# estop.net
KiCad netlist of a schematic drawn in EasyEDA Pro
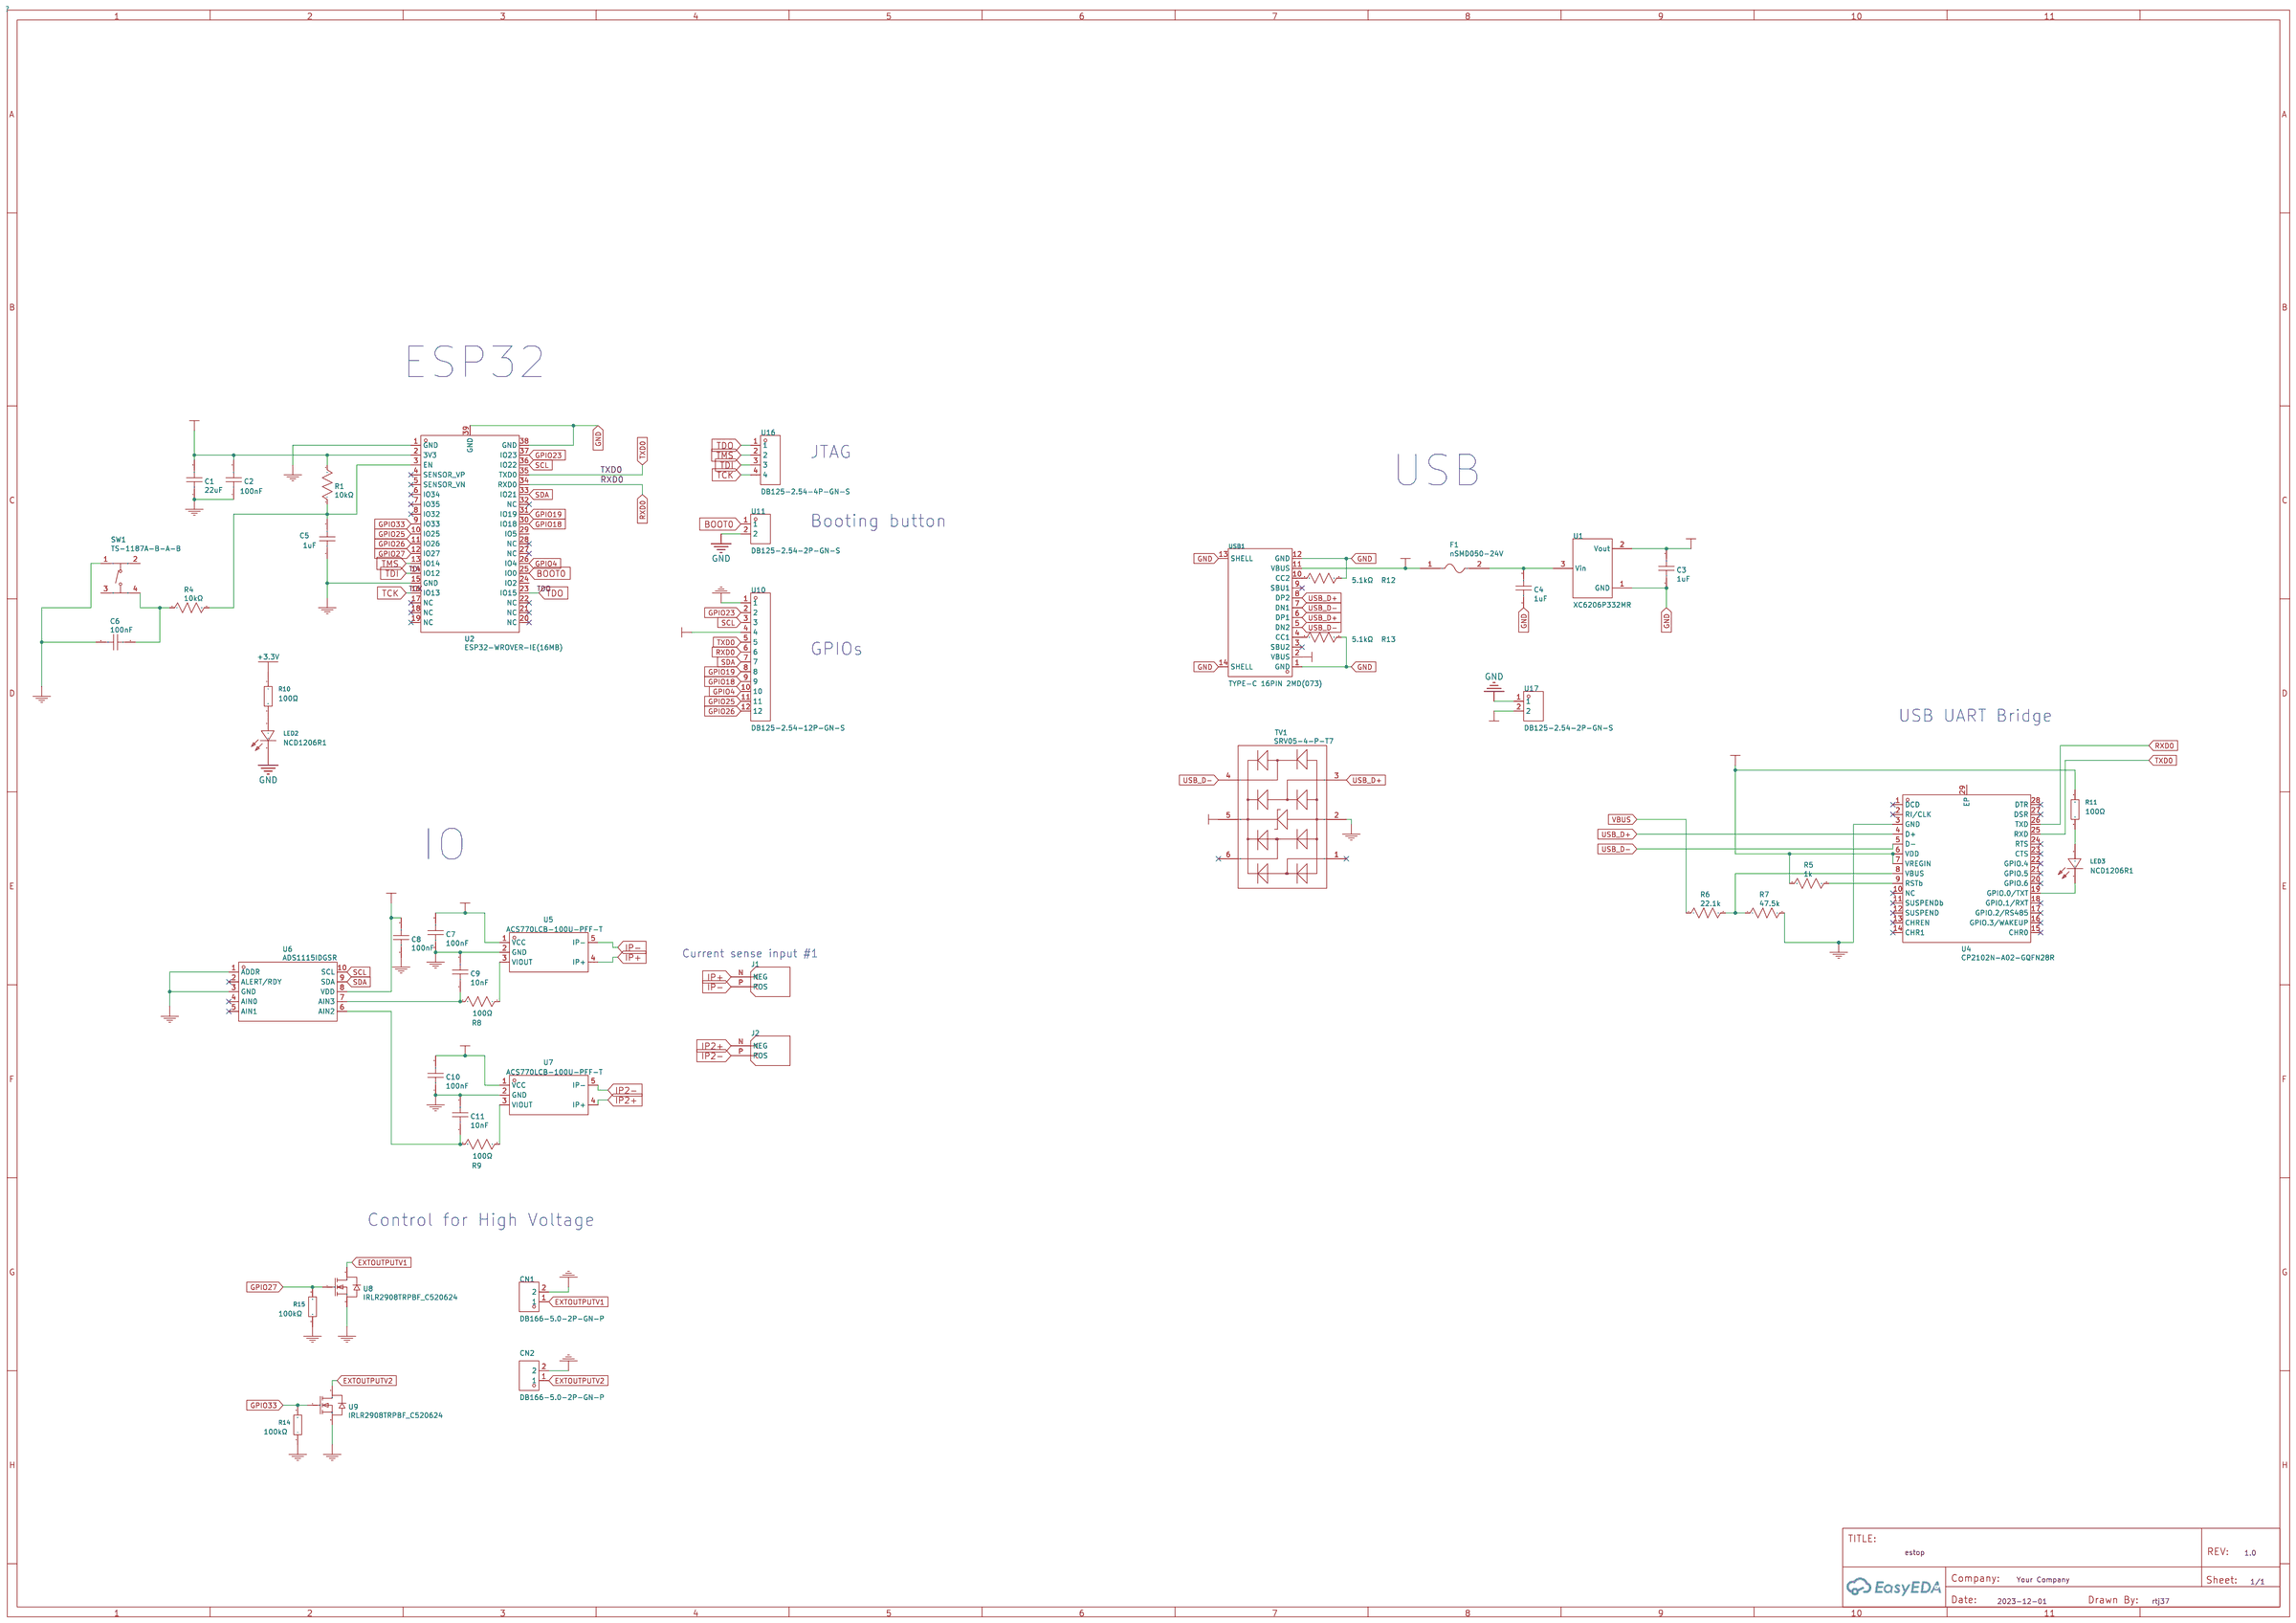
[diagram p0: schematic sheet]

(export (version "E")
  (design (tool "Eeschema 10.0.6"))
  (components
    (comp (ref "C1")
      (value "22uF")
      (footprint "easyedapro:C1206")
      (fields
        (field (name "Manufacturer Part") "CL31A226KAHNNNE")
        (field (name "Manufacturer") "SAMSUNG(三星)")
      )
      (libsource (lib "easyedapro") (part "22u"))
    )
    (comp (ref "C2")
      (value "100nF")
      (footprint "easyedapro:C1206")
      (fields (field (name "Manufacturer Part") "1206B104K500NT") (field (name "Manufacturer") "FH(风华)"))
      (libsource (lib "easyedapro") (part "0.1u"))
    )
    (comp (ref "C3")
      (value "1uF")
      (footprint "easyedapro:C0603")
      (fields (field (name "Manufacturer Part") "1206B105K500NT") (field (name "Manufacturer") "FH(风华)"))
      (libsource (lib "easyedapro") (part "1u"))
    )
    (comp (ref "C4")
      (value "1uF")
      (footprint "easyedapro:C0603")
      (fields (field (name "Manufacturer Part") "1206B105K500NT") (field (name "Manufacturer") "FH(风华)"))
      (libsource (lib "easyedapro") (part "1u"))
    )
    (comp (ref "C5")
      (value "1uF")
      (footprint "easyedapro:C0603")
      (fields (field (name "Manufacturer Part") "1206B105K500NT") (field (name "Manufacturer") "FH(风华)"))
      (libsource (lib "easyedapro") (part "1u"))
    )
    (comp (ref "C6")
      (value "100nF")
      (footprint "easyedapro:C1206")
      (fields (field (name "Manufacturer Part") "1206B104K500NT") (field (name "Manufacturer") "FH(风华)"))
      (libsource (lib "easyedapro") (part "0.1u"))
    )
    (comp (ref "C7")
      (value "100nF")
      (footprint "easyedapro:C1206")
      (fields (field (name "Manufacturer Part") "1206B104K500NT") (field (name "Manufacturer") "FH(风华)"))
      (libsource (lib "easyedapro") (part "0.1u"))
    )
    (comp (ref "C8")
      (value "100nF")
      (footprint "easyedapro:C1206")
      (fields (field (name "Manufacturer Part") "1206B104K500NT") (field (name "Manufacturer") "FH(风华)"))
      (libsource (lib "easyedapro") (part "100n"))
    )
    (comp (ref "C9")
      (value "10nF")
      (footprint "easyedapro:C0805")
      (fields (field (name "Manufacturer Part") "1206B103K102CT") (field (name "Manufacturer") "Walsin(华新科)"))
      (libsource (lib "easyedapro") (part "10n"))
    )
    (comp (ref "C10")
      (value "100nF")
      (footprint "easyedapro:C1206")
      (fields (field (name "Manufacturer Part") "1206B104K500NT") (field (name "Manufacturer") "FH(风华)"))
      (libsource (lib "easyedapro") (part "0.1u"))
    )
    (comp (ref "C11")
      (value "10nF")
      (footprint "easyedapro:C0805")
      (fields (field (name "Manufacturer Part") "1206B103K102CT") (field (name "Manufacturer") "Walsin(华新科)"))
      (libsource (lib "easyedapro") (part "10n"))
    )
    (comp (ref "CN1")
      (value "DB166-5.0-2P-GN-P")
      (footprint "easyedapro:CONN-TH_2P-P5.00_DB166-5.0-2P-GN-P")
      (description "Pitch:5mm Number of Pins:2P")
      (fields (field (name "Manufacturer") "DORABO(地博电气)"))
      (libsource (lib "easyedapro") (part "DB166-5.0-2P-GN-P"))
    )
    (comp (ref "CN2")
      (value "DB166-5.0-2P-GN-P")
      (footprint "easyedapro:CONN-TH_2P-P5.00_DB166-5.0-2P-GN-P")
      (description "Pitch:5mm Number of Pins:2P")
      (fields (field (name "Manufacturer") "DORABO(地博电气)"))
      (libsource (lib "easyedapro") (part "DB166-5.0-2P-GN-P"))
    )
    (comp (ref "F1")
      (value "nSMD050-24V")
      (footprint "easyedapro:F1206")
      (fields (field (name "Manufacturer") "台湾陆海"))
      (libsource (lib "easyedapro") (part "nSMD050-24V"))
    )
    (comp (ref "J1")
      (value "XT90PW-F")
      (footprint "easyedapro:AMASS_XT90PW-F")
      (description "\\nSocket, DC supply, XT90, female, PIN:2, on PCBs, THT\\n")
      (libsource (lib "easyedapro") (part "XT90PW-F"))
    )
    (comp (ref "J2")
      (value "XT90PW-F")
      (footprint "easyedapro:AMASS_XT90PW-F")
      (description "\\nSocket, DC supply, XT90, female, PIN:2, on PCBs, THT\\n")
      (libsource (lib "easyedapro") (part "XT90PW-F"))
    )
    (comp (ref "LED2")
      (value "NCD1206R1")
      (footprint "easyedapro:LED1206-R-RD_RED")
      (fields (field (name "Manufacturer") "国星光电"))
      (libsource (lib "easyedapro") (part "FC-3215HRK-620D"))
    )
    (comp (ref "LED3")
      (value "NCD1206R1")
      (footprint "easyedapro:LED1206-R-RD_RED")
      (fields (field (name "Manufacturer") "国星光电"))
      (libsource (lib "easyedapro") (part "FC-3215HRK-620D"))
    )
    (comp (ref "R1")
      (value "10kΩ")
      (footprint "easyedapro:R1206")
      (fields
        (field (name "Manufacturer Part") "1206W4F1002T5E")
        (field (name "Manufacturer") "UNI-ROYAL(厚声)")
      )
      (libsource (lib "easyedapro") (part "10k"))
    )
    (comp (ref "R4")
      (value "10kΩ")
      (footprint "easyedapro:R1206")
      (fields
        (field (name "Manufacturer Part") "1206W4F1002T5E")
        (field (name "Manufacturer") "UNI-ROYAL(厚声)")
      )
      (libsource (lib "easyedapro") (part "0"))
    )
    (comp (ref "R5") (value "1k") (footprint "easyedapro:R1206") (libsource (lib "easyedapro") (part "1k")))
    (comp (ref "R6")
      (value "22.1k")
      (footprint "easyedapro:R1206")
      (libsource (lib "easyedapro") (part "22.1k"))
    )
    (comp (ref "R7")
      (value "47.5k")
      (footprint "easyedapro:R1206")
      (libsource (lib "easyedapro") (part "47.5k"))
    )
    (comp (ref "R8")
      (value "100Ω")
      (footprint "easyedapro:R0603")
      (fields
        (field (name "Manufacturer Part") "1206W4F1000T5E")
        (field (name "Manufacturer") "UNI-ROYAL(厚声)")
      )
      (libsource (lib "easyedapro") (part "100"))
    )
    (comp (ref "R9")
      (value "100Ω")
      (footprint "easyedapro:R0603")
      (fields
        (field (name "Manufacturer Part") "1206W4F1000T5E")
        (field (name "Manufacturer") "UNI-ROYAL(厚声)")
      )
      (libsource (lib "easyedapro") (part "100"))
    )
    (comp (ref "R10")
      (value "100Ω")
      (footprint "easyedapro:R1206")
      (fields
        (field (name "Manufacturer Part") "1206W4F1000T5E")
        (field (name "Manufacturer") "UNI-ROYAL(厚声)")
      )
      (libsource (lib "easyedapro") (part "1206W4F1000T5E"))
    )
    (comp (ref "R11")
      (value "100Ω")
      (footprint "easyedapro:R1206")
      (fields
        (field (name "Manufacturer Part") "1206W4F1000T5E")
        (field (name "Manufacturer") "UNI-ROYAL(厚声)")
      )
      (libsource (lib "easyedapro") (part "1206W4F1000T5E"))
    )
    (comp (ref "R12")
      (value "5.1kΩ")
      (footprint "easyedapro:R0603")
      (fields
        (field (name "Manufacturer Part") "1206W4F5101T5E")
        (field (name "Manufacturer") "UNI-ROYAL(厚声)")
      )
      (libsource (lib "easyedapro") (part "5.1k"))
    )
    (comp (ref "R13")
      (value "5.1kΩ")
      (footprint "easyedapro:R0603")
      (fields
        (field (name "Manufacturer Part") "1206W4F5101T5E")
        (field (name "Manufacturer") "UNI-ROYAL(厚声)")
      )
      (libsource (lib "easyedapro") (part "5.1k"))
    )
    (comp (ref "R14")
      (value "100kΩ")
      (footprint "easyedapro:R1206")
      (fields
        (field (name "Manufacturer Part") "1206W4F1003T5E")
        (field (name "Manufacturer") "UNI-ROYAL(厚声)")
      )
      (libsource (lib "easyedapro") (part "1206W4F1003T5E"))
    )
    (comp (ref "R15")
      (value "100kΩ")
      (footprint "easyedapro:R1206")
      (fields
        (field (name "Manufacturer Part") "1206W4F1003T5E")
        (field (name "Manufacturer") "UNI-ROYAL(厚声)")
      )
      (libsource (lib "easyedapro") (part "1206W4F1003T5E"))
    )
    (comp (ref "SW1")
      (value "TS-1187A-B-A-B")
      (footprint "easyedapro:SW-SMD_4P-L5.1-W5.1-P3.70-LS6.5-TL-2")
      (fields (field (name "Manufacturer") "XKB Connectivity(中国星坤)"))
      (libsource (lib "easyedapro") (part "TS-1187A-B-A-B"))
    )
    (comp (ref "TV1")
      (value "SRV05-4-P-T7")
      (footprint "easyedapro:SOT-23-6_L2.9-W1.6-P0.95-LS2.8-BR")
      (fields (field (name "Manufacturer") "PROTEK"))
      (libsource (lib "easyedapro") (part "SRV05-4-P-T7"))
    )
    (comp (ref "U1")
      (value "XC6206P332MR")
      (footprint "easyedapro:SOT-23-3_L2.9-W1.6-P1.90-LS2.8-BR")
      (fields (field (name "Manufacturer") "TOREX(特瑞仕)"))
      (libsource (lib "easyedapro") (part "XC6206P332MR"))
    )
    (comp (ref "U2")
      (value "ESP32-WROVER-IE(16MB)")
      (footprint "easyedapro:WIFI-SMD_ESP32-WROVER-E")
      (fields
        (field (name "Manufacturer Part") "ESP32-WROVER-IE-N16R8")
        (field (name "Manufacturer") "ESPRESSIF(乐鑫)")
      )
      (libsource (lib "easyedapro") (part "ESP32-WROVER-IE(16MB)"))
    )
    (comp (ref "U4")
      (value "CP2102N-A02-GQFN28R")
      (footprint "easyedapro:QFN-28_L5.0-W5.0-P0.50-TL-EP3.3")
      (fields (field (name "Manufacturer") "SILICON LABS(芯科)"))
      (libsource (lib "easyedapro") (part "CP2102N-A02-GQFN28R"))
    )
    (comp (ref "U5")
      (value "ACS770LCB-100U-PFF-T")
      (footprint "easyedapro:SENSOR-TH_ACS770LCB-100U-PFF-T")
      (fields (field (name "Manufacturer") "ALLEGRO(美国埃戈罗)"))
      (libsource (lib "easyedapro") (part "ACS770LCB-100U-PFF-T"))
    )
    (comp (ref "U6")
      (value "ADS1115IDGSR")
      (footprint "easyedapro:MSOP-10_L3.0-W3.0-P0.50-LS5.0-BL")
      (fields (field (name "Manufacturer") "TI(德州仪器)"))
      (libsource (lib "easyedapro") (part "ADS1115IDGSR"))
    )
    (comp (ref "U7")
      (value "ACS770LCB-100U-PFF-T")
      (footprint "easyedapro:SENSOR-TH_ACS770LCB-100U-PFF-T")
      (fields (field (name "Manufacturer") "ALLEGRO(美国埃戈罗)"))
      (libsource (lib "easyedapro") (part "ACS770LCB-100U-PFF-T"))
    )
    (comp (ref "U8")
      (value "IRLR2908TRPBF_C520624")
      (footprint "easyedapro:TO-252-3_L6.5-W6.1-P4.58-LS9.9-BR")
      (fields
        (field (name "Manufacturer Part") "IRLR2908TRPBF")
        (field (name "Manufacturer") "Infineon(英飞凌)")
      )
      (libsource (lib "easyedapro") (part "IRLR2908TRPBF_C520624"))
    )
    (comp (ref "U9")
      (value "IRLR2908TRPBF_C520624")
      (footprint "easyedapro:TO-252-3_L6.5-W6.1-P4.58-LS9.9-BR")
      (fields
        (field (name "Manufacturer Part") "IRLR2908TRPBF")
        (field (name "Manufacturer") "Infineon(英飞凌)")
      )
      (libsource (lib "easyedapro") (part "IRLR2908TRPBF_C520624"))
    )
    (comp (ref "U10")
      (value "DB125-2.54-12P-GN-S")
      (footprint "easyedapro:CONN-TH_DB125-2.54-12P-GN")
      (fields (field (name "Manufacturer") "DORABO(地博电气)"))
      (libsource (lib "easyedapro") (part "DB125-2.54-12P-GN"))
    )
    (comp (ref "U11")
      (value "DB125-2.54-2P-GN-S")
      (footprint "easyedapro:CONN-TH_DB125-2.54-2P-GN")
      (fields (field (name "Manufacturer") "DORABO(地博电气)"))
      (libsource (lib "easyedapro") (part "DB125-2.54-2P-GN"))
    )
    (comp (ref "U16")
      (value "DB125-2.54-4P-GN-S")
      (footprint "easyedapro:CONN-TH_DB125-2.54-4P-GN")
      (fields (field (name "Manufacturer") "DORABO(地博电气)"))
      (libsource (lib "easyedapro") (part "DB125-2.54-4P-GN"))
    )
    (comp (ref "U17")
      (value "DB125-2.54-2P-GN-S")
      (footprint "easyedapro:CONN-TH_DB125-2.54-2P-GN")
      (fields (field (name "Manufacturer") "DORABO(地博电气)"))
      (libsource (lib "easyedapro") (part "DB125-2.54-2P-GN"))
    )
    (comp (ref "USB1")
      (value "TYPE-C 16PIN 2MD(073)")
      (footprint "easyedapro:USB-C-SMD_TYPE-C-6PIN-2MD-073")
      (fields (field (name "Manufacturer") "SHOU HAN(首韩)"))
      (libsource (lib "easyedapro") (part "TYPE-C 16PIN 2MD(073)"))
    )
  )
  (nets
    (net (code "1") (name "+3.3V") (class "Default")
      (node (ref "C1") (pin "2") (pinfunction "2_2") (pintype "unspecified"))
      (node (ref "C2") (pin "2") (pinfunction "2_2") (pintype "unspecified"))
      (node (ref "C3") (pin "2") (pinfunction "2_2") (pintype "unspecified"))
      (node (ref "C8") (pin "2") (pinfunction "2_2") (pintype "unspecified"))
      (node (ref "R1") (pin "2") (pinfunction "2_2") (pintype "unspecified"))
      (node (ref "R10") (pin "1") (pinfunction "1_1") (pintype "input"))
      (node (ref "R11") (pin "1") (pinfunction "1_1") (pintype "input"))
      (node (ref "R5") (pin "1") (pinfunction "1_1") (pintype "unspecified"))
      (node (ref "U1") (pin "2") (pinfunction "Vout_2") (pintype "unspecified"))
      (node (ref "U10") (pin "4") (pinfunction "4_4") (pintype "unspecified"))
      (node (ref "U2") (pin "2") (pinfunction "3V3_2") (pintype "unspecified"))
      (node (ref "U4") (pin "6") (pinfunction "VDD_6") (pintype "unspecified"))
      (node (ref "U4") (pin "7") (pinfunction "VREGIN_7") (pintype "unspecified"))
      (node (ref "U6") (pin "8") (pinfunction "VDD_8") (pintype "unspecified"))
    )
    (net (code "2") (name "BOOT0") (class "Default")
      (node (ref "U11") (pin "1") (pinfunction "1_1") (pintype "unspecified"))
      (node (ref "U2") (pin "25") (pinfunction "IO0_25") (pintype "unspecified"))
    )
    (net (code "3") (name "EXTOUTPUTV1") (class "Default")
      (node (ref "CN1") (pin "1") (pinfunction "1_1") (pintype "unspecified"))
      (node (ref "U8") (pin "2") (pinfunction "D_2") (pintype "unspecified"))
    )
    (net (code "4") (name "EXTOUTPUTV2") (class "Default")
      (node (ref "CN2") (pin "1") (pinfunction "1_1") (pintype "unspecified"))
      (node (ref "U9") (pin "2") (pinfunction "D_2") (pintype "unspecified"))
    )
    (net (code "5") (name "GND") (class "Default")
      (node (ref "C1") (pin "1") (pinfunction "1_1") (pintype "unspecified"))
      (node (ref "C10") (pin "1") (pinfunction "1_1") (pintype "unspecified"))
      (node (ref "C11") (pin "2") (pinfunction "2_2") (pintype "unspecified"))
      (node (ref "C2") (pin "1") (pinfunction "1_1") (pintype "unspecified"))
      (node (ref "C3") (pin "1") (pinfunction "1_1") (pintype "unspecified"))
      (node (ref "C4") (pin "1") (pinfunction "1_1") (pintype "unspecified"))
      (node (ref "C5") (pin "1") (pinfunction "1_1") (pintype "unspecified"))
      (node (ref "C6") (pin "1") (pinfunction "1_1") (pintype "unspecified"))
      (node (ref "C7") (pin "1") (pinfunction "1_1") (pintype "unspecified"))
      (node (ref "C8") (pin "1") (pinfunction "1_1") (pintype "unspecified"))
      (node (ref "C9") (pin "2") (pinfunction "2_2") (pintype "unspecified"))
      (node (ref "CN1") (pin "2") (pinfunction "2_2") (pintype "unspecified"))
      (node (ref "CN2") (pin "2") (pinfunction "2_2") (pintype "unspecified"))
      (node (ref "LED2") (pin "2") (pinfunction "K_2") (pintype "input"))
      (node (ref "R12") (pin "2") (pinfunction "2_2") (pintype "unspecified"))
      (node (ref "R13") (pin "2") (pinfunction "2_2") (pintype "unspecified"))
      (node (ref "R14") (pin "1") (pinfunction "1_1") (pintype "input"))
      (node (ref "R15") (pin "1") (pinfunction "1_1") (pintype "input"))
      (node (ref "R7") (pin "2") (pinfunction "2_2") (pintype "unspecified"))
      (node (ref "SW1") (pin "1") (pinfunction "A_1") (pintype "unspecified"))
      (node (ref "TV1") (pin "2") (pinfunction "2_2") (pintype "input"))
      (node (ref "U1") (pin "1") (pinfunction "GND_1") (pintype "unspecified"))
      (node (ref "U10") (pin "1") (pinfunction "1_1") (pintype "unspecified"))
      (node (ref "U11") (pin "2") (pinfunction "2_2") (pintype "unspecified"))
      (node (ref "U17") (pin "1") (pinfunction "1_1") (pintype "unspecified"))
      (node (ref "U2") (pin "1") (pinfunction "GND_1") (pintype "unspecified"))
      (node (ref "U2") (pin "15") (pinfunction "GND_15") (pintype "unspecified"))
      (node (ref "U2") (pin "38") (pinfunction "GND_38") (pintype "unspecified"))
      (node (ref "U2") (pin "39") (pinfunction "GND_39") (pintype "unspecified"))
      (node (ref "U4") (pin "3") (pinfunction "GND_3") (pintype "unspecified"))
      (node (ref "U5") (pin "2") (pinfunction "GND_2") (pintype "unspecified"))
      (node (ref "U6") (pin "1") (pinfunction "ADDR_1") (pintype "unspecified"))
      (node (ref "U6") (pin "3") (pinfunction "GND_3") (pintype "unspecified"))
      (node (ref "U7") (pin "2") (pinfunction "GND_2") (pintype "unspecified"))
      (node (ref "U8") (pin "3") (pinfunction "S_3") (pintype "unspecified"))
      (node (ref "U9") (pin "3") (pinfunction "S_3") (pintype "unspecified"))
      (node (ref "USB1") (pin "1") (pinfunction "GND_1") (pintype "input"))
      (node (ref "USB1") (pin "12") (pinfunction "GND_12") (pintype "input"))
      (node (ref "USB1") (pin "13") (pinfunction "SHELL_13") (pintype "input"))
      (node (ref "USB1") (pin "14") (pinfunction "SHELL_14") (pintype "input"))
    )
    (net (code "6") (name "GPIO4") (class "Default")
      (node (ref "U10") (pin "10") (pinfunction "10_10") (pintype "unspecified"))
      (node (ref "U2") (pin "26") (pinfunction "IO4_26") (pintype "unspecified"))
    )
    (net (code "7") (name "GPIO18") (class "Default")
      (node (ref "U10") (pin "9") (pinfunction "9_9") (pintype "unspecified"))
      (node (ref "U2") (pin "30") (pinfunction "IO18_30") (pintype "unspecified"))
    )
    (net (code "8") (name "GPIO19") (class "Default")
      (node (ref "U10") (pin "8") (pinfunction "8_8") (pintype "unspecified"))
      (node (ref "U2") (pin "31") (pinfunction "IO19_31") (pintype "unspecified"))
    )
    (net (code "9") (name "GPIO23") (class "Default")
      (node (ref "U10") (pin "2") (pinfunction "2_2") (pintype "unspecified"))
      (node (ref "U2") (pin "37") (pinfunction "IO23_37") (pintype "unspecified"))
    )
    (net (code "10") (name "GPIO25") (class "Default")
      (node (ref "U10") (pin "11") (pinfunction "11_11") (pintype "unspecified"))
      (node (ref "U2") (pin "10") (pinfunction "IO25_10") (pintype "unspecified"))
    )
    (net (code "11") (name "GPIO26") (class "Default")
      (node (ref "U10") (pin "12") (pinfunction "12_12") (pintype "unspecified"))
      (node (ref "U2") (pin "11") (pinfunction "IO26_11") (pintype "unspecified"))
    )
    (net (code "12") (name "GPIO27") (class "Default")
      (node (ref "R15") (pin "2") (pinfunction "2_2") (pintype "input"))
      (node (ref "U2") (pin "12") (pinfunction "IO27_12") (pintype "unspecified"))
      (node (ref "U8") (pin "1") (pinfunction "G_1") (pintype "unspecified"))
    )
    (net (code "13") (name "GPIO33") (class "Default")
      (node (ref "R14") (pin "2") (pinfunction "2_2") (pintype "input"))
      (node (ref "U2") (pin "9") (pinfunction "IO33_9") (pintype "unspecified"))
      (node (ref "U9") (pin "1") (pinfunction "G_1") (pintype "unspecified"))
    )
    (net (code "14") (name "IP+") (class "Default")
      (node (ref "J1") (pin "N") (pinfunction "NEG_N") (pintype "unspecified"))
      (node (ref "U5") (pin "4") (pinfunction "IP+_4") (pintype "unspecified"))
    )
    (net (code "15") (name "IP-") (class "Default")
      (node (ref "J1") (pin "P") (pinfunction "POS_P") (pintype "unspecified"))
      (node (ref "U5") (pin "5") (pinfunction "IP-_5") (pintype "unspecified"))
    )
    (net (code "16") (name "IP2+") (class "Default")
      (node (ref "J2") (pin "N") (pinfunction "NEG_N") (pintype "unspecified"))
      (node (ref "U7") (pin "4") (pinfunction "IP+_4") (pintype "unspecified"))
    )
    (net (code "17") (name "IP2-") (class "Default")
      (node (ref "J2") (pin "P") (pinfunction "POS_P") (pintype "unspecified"))
      (node (ref "U7") (pin "5") (pinfunction "IP-_5") (pintype "unspecified"))
    )
    (net (code "18") (name "Net-(LED2-A)") (class "Default")
      (node (ref "LED2") (pin "1") (pinfunction "A_1") (pintype "input"))
      (node (ref "R10") (pin "2") (pinfunction "2_2") (pintype "input"))
    )
    (net (code "19") (name "Net-(LED3-A)") (class "Default")
      (node (ref "LED3") (pin "1") (pinfunction "A_1") (pintype "input"))
      (node (ref "R11") (pin "2") (pinfunction "2_2") (pintype "input"))
    )
    (net (code "20") (name "Net-(LED3-K)") (class "Default")
      (node (ref "LED3") (pin "2") (pinfunction "K_2") (pintype "input"))
      (node (ref "U4") (pin "19") (pinfunction "GPIO.0/TXT_19") (pintype "unspecified"))
    )
    (net (code "21") (name "Net-(SW1-D)") (class "Default")
      (node (ref "C6") (pin "2") (pinfunction "2_2") (pintype "unspecified"))
      (node (ref "R4") (pin "1") (pinfunction "1_1") (pintype "unspecified"))
      (node (ref "SW1") (pin "4") (pinfunction "D_4") (pintype "unspecified"))
    )
    (net (code "22") (name "Net-(U1-Vin)") (class "Default")
      (node (ref "C4") (pin "2") (pinfunction "2_2") (pintype "unspecified"))
      (node (ref "F1") (pin "2") (pinfunction "2_2") (pintype "unspecified"))
      (node (ref "U1") (pin "3") (pinfunction "Vin_3") (pintype "unspecified"))
    )
    (net (code "23") (name "Net-(U2-EN)") (class "Default")
      (node (ref "C5") (pin "2") (pinfunction "2_2") (pintype "unspecified"))
      (node (ref "R1") (pin "1") (pinfunction "1_1") (pintype "unspecified"))
      (node (ref "R4") (pin "2") (pinfunction "2_2") (pintype "unspecified"))
      (node (ref "U2") (pin "3") (pinfunction "EN_3") (pintype "unspecified"))
    )
    (net (code "24") (name "Net-(U4-RSTb)") (class "Default")
      (node (ref "R5") (pin "2") (pinfunction "2_2") (pintype "unspecified"))
      (node (ref "U4") (pin "9") (pinfunction "RSTb_9") (pintype "unspecified"))
    )
    (net (code "25") (name "Net-(U4-VBUS)") (class "Default")
      (node (ref "R6") (pin "2") (pinfunction "2_2") (pintype "unspecified"))
      (node (ref "R7") (pin "1") (pinfunction "1_1") (pintype "unspecified"))
      (node (ref "U4") (pin "8") (pinfunction "VBUS_8") (pintype "unspecified"))
    )
    (net (code "26") (name "Net-(U5-VIOUT)") (class "Default")
      (node (ref "R8") (pin "1") (pinfunction "1_1") (pintype "unspecified"))
      (node (ref "U5") (pin "3") (pinfunction "VIOUT_3") (pintype "unspecified"))
    )
    (net (code "27") (name "Net-(U6-AIN2)") (class "Default")
      (node (ref "C11") (pin "1") (pinfunction "1_1") (pintype "unspecified"))
      (node (ref "R9") (pin "2") (pinfunction "2_2") (pintype "unspecified"))
      (node (ref "U6") (pin "6") (pinfunction "AIN2_6") (pintype "unspecified"))
    )
    (net (code "28") (name "Net-(U6-AIN3)") (class "Default")
      (node (ref "C9") (pin "1") (pinfunction "1_1") (pintype "unspecified"))
      (node (ref "R8") (pin "2") (pinfunction "2_2") (pintype "unspecified"))
      (node (ref "U6") (pin "7") (pinfunction "AIN3_7") (pintype "unspecified"))
    )
    (net (code "29") (name "Net-(U7-VIOUT)") (class "Default")
      (node (ref "R9") (pin "1") (pinfunction "1_1") (pintype "unspecified"))
      (node (ref "U7") (pin "3") (pinfunction "VIOUT_3") (pintype "unspecified"))
    )
    (net (code "30") (name "Net-(USB1-CC1)") (class "Default")
      (node (ref "R13") (pin "1") (pinfunction "1_1") (pintype "unspecified"))
      (node (ref "USB1") (pin "4") (pinfunction "CC1_4") (pintype "input"))
    )
    (net (code "31") (name "Net-(USB1-CC2)") (class "Default")
      (node (ref "R12") (pin "1") (pinfunction "1_1") (pintype "unspecified"))
      (node (ref "USB1") (pin "10") (pinfunction "CC2_10") (pintype "input"))
    )
    (net (code "32") (name "RXD0") (class "Default")
      (node (ref "U10") (pin "6") (pinfunction "6_6") (pintype "unspecified"))
      (node (ref "U2") (pin "34") (pinfunction "RXD0_34") (pintype "unspecified"))
      (node (ref "U4") (pin "26") (pinfunction "TXD_26") (pintype "unspecified"))
    )
    (net (code "33") (name "SCL") (class "Default")
      (node (ref "U10") (pin "3") (pinfunction "3_3") (pintype "unspecified"))
      (node (ref "U2") (pin "36") (pinfunction "IO22_36") (pintype "unspecified"))
      (node (ref "U6") (pin "10") (pinfunction "SCL_10") (pintype "unspecified"))
    )
    (net (code "34") (name "SDA") (class "Default")
      (node (ref "U10") (pin "7") (pinfunction "7_7") (pintype "unspecified"))
      (node (ref "U2") (pin "33") (pinfunction "IO21_33") (pintype "unspecified"))
      (node (ref "U6") (pin "9") (pinfunction "SDA_9") (pintype "unspecified"))
    )
    (net (code "35") (name "TCK") (class "Default")
      (node (ref "U16") (pin "4") (pinfunction "4_4") (pintype "unspecified"))
      (node (ref "U2") (pin "16") (pinfunction "IO13_16") (pintype "unspecified"))
    )
    (net (code "36") (name "TDI") (class "Default")
      (node (ref "U16") (pin "3") (pinfunction "3_3") (pintype "unspecified"))
      (node (ref "U2") (pin "14") (pinfunction "IO12_14") (pintype "unspecified"))
    )
    (net (code "37") (name "TDO") (class "Default")
      (node (ref "U16") (pin "1") (pinfunction "1_1") (pintype "unspecified"))
      (node (ref "U2") (pin "23") (pinfunction "IO15_23") (pintype "unspecified"))
    )
    (net (code "38") (name "TMS") (class "Default")
      (node (ref "U16") (pin "2") (pinfunction "2_2") (pintype "unspecified"))
      (node (ref "U2") (pin "13") (pinfunction "IO14_13") (pintype "unspecified"))
    )
    (net (code "39") (name "TXD0") (class "Default")
      (node (ref "U10") (pin "5") (pinfunction "5_5") (pintype "unspecified"))
      (node (ref "U2") (pin "35") (pinfunction "TXD0_35") (pintype "unspecified"))
      (node (ref "U4") (pin "25") (pinfunction "RXD_25") (pintype "unspecified"))
    )
    (net (code "40") (name "USB_D+") (class "Default")
      (node (ref "TV1") (pin "3") (pinfunction "3_3") (pintype "input"))
      (node (ref "U4") (pin "4") (pinfunction "D+_4") (pintype "unspecified"))
      (node (ref "USB1") (pin "6") (pinfunction "DP1_6") (pintype "input"))
      (node (ref "USB1") (pin "8") (pinfunction "DP2_8") (pintype "input"))
    )
    (net (code "41") (name "USB_D-") (class "Default")
      (node (ref "TV1") (pin "4") (pinfunction "4_4") (pintype "input"))
      (node (ref "U4") (pin "5") (pinfunction "D-_5") (pintype "unspecified"))
      (node (ref "USB1") (pin "5") (pinfunction "DN2_5") (pintype "input"))
      (node (ref "USB1") (pin "7") (pinfunction "DN1_7") (pintype "input"))
    )
    (net (code "42") (name "VBUS") (class "Default")
      (node (ref "C10") (pin "2") (pinfunction "2_2") (pintype "unspecified"))
      (node (ref "C7") (pin "2") (pinfunction "2_2") (pintype "unspecified"))
      (node (ref "F1") (pin "1") (pinfunction "1_1") (pintype "unspecified"))
      (node (ref "R6") (pin "1") (pinfunction "1_1") (pintype "unspecified"))
      (node (ref "TV1") (pin "5") (pinfunction "5_5") (pintype "input"))
      (node (ref "U17") (pin "2") (pinfunction "2_2") (pintype "unspecified"))
      (node (ref "U5") (pin "1") (pinfunction "VCC_1") (pintype "unspecified"))
      (node (ref "U7") (pin "1") (pinfunction "VCC_1") (pintype "unspecified"))
      (node (ref "USB1") (pin "11") (pinfunction "VBUS_11") (pintype "input"))
      (node (ref "USB1") (pin "2") (pinfunction "VBUS_2") (pintype "input"))
    )
    (net (code "43") (name "unconnected-(SW1-B-Pad2)") (class "Default")
      (node (ref "SW1") (pin "2") (pinfunction "B_2") (pintype "unspecified"))
    )
    (net (code "44") (name "unconnected-(SW1-C-Pad3)") (class "Default")
      (node (ref "SW1") (pin "3") (pinfunction "C_3") (pintype "unspecified"))
    )
    (net (code "45") (name "unconnected-(TV1-Pad1)") (class "Default")
      (node (ref "TV1") (pin "1") (pinfunction "1_1") (pintype "input+no_connect"))
    )
    (net (code "46") (name "unconnected-(TV1-Pad6)") (class "Default")
      (node (ref "TV1") (pin "6") (pinfunction "6_6") (pintype "input+no_connect"))
    )
    (net (code "47") (name "unconnected-(U2-IO2-Pad24)") (class "Default")
      (node (ref "U2") (pin "24") (pinfunction "IO2_24") (pintype "unspecified"))
    )
    (net (code "48") (name "unconnected-(U2-IO5-Pad29)") (class "Default")
      (node (ref "U2") (pin "29") (pinfunction "IO5_29") (pintype "unspecified"))
    )
    (net (code "49") (name "unconnected-(U2-IO32-Pad8)") (class "Default")
      (node (ref "U2") (pin "8") (pinfunction "IO32_8") (pintype "unspecified+no_connect"))
    )
    (net (code "50") (name "unconnected-(U2-IO34-Pad6)") (class "Default")
      (node (ref "U2") (pin "6") (pinfunction "IO34_6") (pintype "unspecified+no_connect"))
    )
    (net (code "51") (name "unconnected-(U2-IO35-Pad7)") (class "Default")
      (node (ref "U2") (pin "7") (pinfunction "IO35_7") (pintype "unspecified+no_connect"))
    )
    (net (code "52") (name "unconnected-(U2-NC-Pad17)") (class "Default")
      (node (ref "U2") (pin "17") (pinfunction "NC_17") (pintype "unspecified+no_connect"))
    )
    (net (code "53") (name "unconnected-(U2-NC-Pad18)") (class "Default")
      (node (ref "U2") (pin "18") (pinfunction "NC_18") (pintype "unspecified+no_connect"))
    )
    (net (code "54") (name "unconnected-(U2-NC-Pad19)") (class "Default")
      (node (ref "U2") (pin "19") (pinfunction "NC_19") (pintype "unspecified+no_connect"))
    )
    (net (code "55") (name "unconnected-(U2-NC-Pad20)") (class "Default")
      (node (ref "U2") (pin "20") (pinfunction "NC_20") (pintype "unspecified+no_connect"))
    )
    (net (code "56") (name "unconnected-(U2-NC-Pad21)") (class "Default")
      (node (ref "U2") (pin "21") (pinfunction "NC_21") (pintype "unspecified+no_connect"))
    )
    (net (code "57") (name "unconnected-(U2-NC-Pad22)") (class "Default")
      (node (ref "U2") (pin "22") (pinfunction "NC_22") (pintype "unspecified+no_connect"))
    )
    (net (code "58") (name "unconnected-(U2-NC-Pad27)") (class "Default")
      (node (ref "U2") (pin "27") (pinfunction "NC_27") (pintype "unspecified+no_connect"))
    )
    (net (code "59") (name "unconnected-(U2-NC-Pad28)") (class "Default")
      (node (ref "U2") (pin "28") (pinfunction "NC_28") (pintype "unspecified+no_connect"))
    )
    (net (code "60") (name "unconnected-(U2-NC-Pad32)") (class "Default")
      (node (ref "U2") (pin "32") (pinfunction "NC_32") (pintype "unspecified+no_connect"))
    )
    (net (code "61") (name "unconnected-(U2-SENSOR_VN-Pad5)") (class "Default")
      (node (ref "U2") (pin "5") (pinfunction "SENSOR_VN_5") (pintype "unspecified+no_connect"))
    )
    (net (code "62") (name "unconnected-(U2-SENSOR_VP-Pad4)") (class "Default")
      (node (ref "U2") (pin "4") (pinfunction "SENSOR_VP_4") (pintype "unspecified+no_connect"))
    )
    (net (code "63") (name "unconnected-(U4-CHR0-Pad15)") (class "Default")
      (node (ref "U4") (pin "15") (pinfunction "CHR0_15") (pintype "unspecified+no_connect"))
    )
    (net (code "64") (name "unconnected-(U4-CHR1-Pad14)") (class "Default")
      (node (ref "U4") (pin "14") (pinfunction "CHR1_14") (pintype "unspecified+no_connect"))
    )
    (net (code "65") (name "unconnected-(U4-CHREN-Pad13)") (class "Default")
      (node (ref "U4") (pin "13") (pinfunction "CHREN_13") (pintype "unspecified+no_connect"))
    )
    (net (code "66") (name "unconnected-(U4-CTS-Pad23)") (class "Default")
      (node (ref "U4") (pin "23") (pinfunction "CTS_23") (pintype "unspecified+no_connect"))
    )
    (net (code "67") (name "unconnected-(U4-DCD-Pad1)") (class "Default")
      (node (ref "U4") (pin "1") (pinfunction "DCD_1") (pintype "unspecified+no_connect"))
    )
    (net (code "68") (name "unconnected-(U4-DSR-Pad27)") (class "Default")
      (node (ref "U4") (pin "27") (pinfunction "DSR_27") (pintype "unspecified+no_connect"))
    )
    (net (code "69") (name "unconnected-(U4-DTR-Pad28)") (class "Default")
      (node (ref "U4") (pin "28") (pinfunction "DTR_28") (pintype "unspecified+no_connect"))
    )
    (net (code "70") (name "unconnected-(U4-EP-Pad29)") (class "Default")
      (node (ref "U4") (pin "29") (pinfunction "EP_29") (pintype "unspecified"))
    )
    (net (code "71") (name "unconnected-(U4-GPIO.1{slash}RXT-Pad18)") (class "Default")
      (node (ref "U4") (pin "18") (pinfunction "GPIO.1/RXT_18") (pintype "unspecified+no_connect"))
    )
    (net (code "72") (name "unconnected-(U4-GPIO.2{slash}RS485-Pad17)") (class "Default")
      (node (ref "U4") (pin "17") (pinfunction "GPIO.2/RS485_17") (pintype "unspecified+no_connect"))
    )
    (net (code "73") (name "unconnected-(U4-GPIO.3{slash}WAKEUP-Pad16)") (class "Default")
      (node (ref "U4") (pin "16") (pinfunction "GPIO.3/WAKEUP_16") (pintype "unspecified+no_connect"))
    )
    (net (code "74") (name "unconnected-(U4-GPIO.4-Pad22)") (class "Default")
      (node (ref "U4") (pin "22") (pinfunction "GPIO.4_22") (pintype "unspecified+no_connect"))
    )
    (net (code "75") (name "unconnected-(U4-GPIO.5-Pad21)") (class "Default")
      (node (ref "U4") (pin "21") (pinfunction "GPIO.5_21") (pintype "unspecified+no_connect"))
    )
    (net (code "76") (name "unconnected-(U4-GPIO.6-Pad20)") (class "Default")
      (node (ref "U4") (pin "20") (pinfunction "GPIO.6_20") (pintype "unspecified+no_connect"))
    )
    (net (code "77") (name "unconnected-(U4-NC-Pad10)") (class "Default")
      (node (ref "U4") (pin "10") (pinfunction "NC_10") (pintype "unspecified+no_connect"))
    )
    (net (code "78") (name "unconnected-(U4-RI{slash}CLK-Pad2)") (class "Default")
      (node (ref "U4") (pin "2") (pinfunction "RI/CLK_2") (pintype "unspecified+no_connect"))
    )
    (net (code "79") (name "unconnected-(U4-RTS-Pad24)") (class "Default")
      (node (ref "U4") (pin "24") (pinfunction "RTS_24") (pintype "unspecified+no_connect"))
    )
    (net (code "80") (name "unconnected-(U4-SUSPEND-Pad12)") (class "Default")
      (node (ref "U4") (pin "12") (pinfunction "SUSPEND_12") (pintype "unspecified+no_connect"))
    )
    (net (code "81") (name "unconnected-(U4-SUSPENDb-Pad11)") (class "Default")
      (node (ref "U4") (pin "11") (pinfunction "SUSPENDb_11") (pintype "unspecified+no_connect"))
    )
    (net (code "82") (name "unconnected-(U6-AIN0-Pad4)") (class "Default")
      (node (ref "U6") (pin "4") (pinfunction "AIN0_4") (pintype "unspecified+no_connect"))
    )
    (net (code "83") (name "unconnected-(U6-AIN1-Pad5)") (class "Default")
      (node (ref "U6") (pin "5") (pinfunction "AIN1_5") (pintype "unspecified+no_connect"))
    )
    (net (code "84") (name "unconnected-(U6-ALERT{slash}RDY-Pad2)") (class "Default")
      (node (ref "U6") (pin "2") (pinfunction "ALERT/RDY_2") (pintype "unspecified+no_connect"))
    )
    (net (code "85") (name "unconnected-(USB1-SBU1-Pad9)") (class "Default")
      (node (ref "USB1") (pin "9") (pinfunction "SBU1_9") (pintype "input+no_connect"))
    )
    (net (code "86") (name "unconnected-(USB1-SBU2-Pad3)") (class "Default")
      (node (ref "USB1") (pin "3") (pinfunction "SBU2_3") (pintype "input+no_connect"))
    )
  )
)
